# CAN.net
KiCad netlist of a schematic drawn in Altium Designer
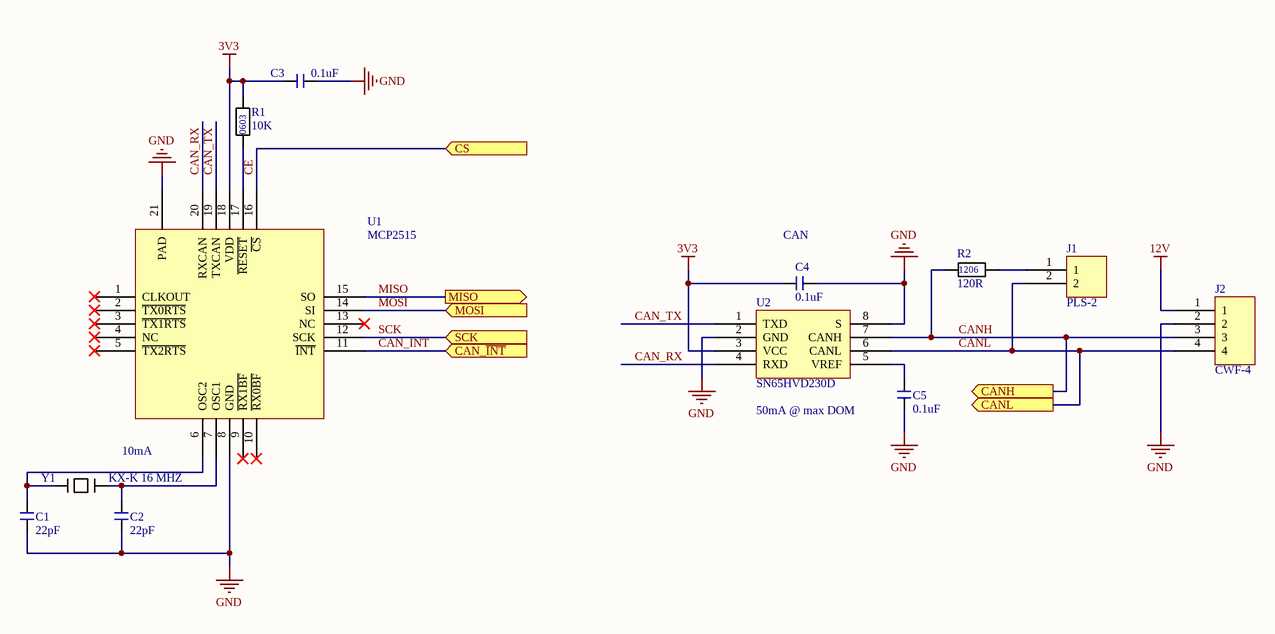
[diagram p0: CAN.SchDoc]

(export (version "E")
  (design (tool "Eeschema 10.0.6"))
  (components
    (comp (ref "C1") (value "22pF") (footprint "CHIP_C_0603") (libsource (lib "Popular") (part "CHIP_C")))
    (comp (ref "C2") (value "22pF") (footprint "CHIP_C_0603") (libsource (lib "Popular") (part "CHIP_C")))
    (comp (ref "C3") (value "0.1uF") (footprint "CHIP_C_0603") (libsource (lib "Popular") (part "CHIP_C")))
    (comp (ref "C4") (value "0.1uF") (footprint "CHIP_C_0603") (libsource (lib "Popular") (part "CHIP_C")))
    (comp (ref "C5") (value "0.1uF") (footprint "CHIP_C_0603") (libsource (lib "Popular") (part "CHIP_C")))
    (comp (ref "J1")
      (value "PLS-2")
      (footprint "PLS-2")
      (description "Connector")
      (libsource (lib "Popular") (part "PLS-2"))
    )
    (comp (ref "J2") (value "CWF-4") (footprint "CWF-4") (libsource (lib "Popular") (part "CWF-4")))
    (comp (ref "R1") (value "10K") (footprint "CHIP_R_0603") (libsource (lib "Popular") (part "RES_0603")))
    (comp (ref "R2") (value "120R") (footprint "CHIP_R_1206") (libsource (lib "Popular") (part "RES_1206")))
    (comp (ref "U1") (value "MCP2515") (footprint "QFN20") (libsource (lib "Popular") (part "MCP2515_QFN")))
    (comp (ref "U2") (value "SN65HVD230D") (footprint "SOIC8") (libsource (lib "Popular") (part "TJA1050")))
    (comp (ref "Y1")
      (value "KX-K 16 MHZ")
      (footprint "CHIP_CRYSTAL_5032")
      (libsource (lib "Popular") (part "Quartz"))
    )
  )
  (nets
    (net (code "1") (name "/CANH") (class "Default")
      (node (ref "J2") (pin "3") (pinfunction "3_3") (pintype "passive"))
      (node (ref "R2") (pin "1") (pinfunction "1_1") (pintype "passive"))
      (node (ref "U2") (pin "7") (pinfunction "CANH_7") (pintype "passive"))
    )
    (net (code "2") (name "/CANL") (class "Default")
      (node (ref "J1") (pin "2") (pinfunction "2_2") (pintype "passive"))
      (node (ref "J2") (pin "4") (pinfunction "4_4") (pintype "passive"))
      (node (ref "U2") (pin "6") (pinfunction "CANL_6") (pintype "passive"))
    )
    (net (code "3") (name "/CAN_RX") (class "Default")
      (node (ref "U1") (pin "20") (pinfunction "RXCAN_20") (pintype "passive"))
      (node (ref "U2") (pin "4") (pinfunction "RXD_4") (pintype "passive"))
    )
    (net (code "4") (name "/CAN_TX") (class "Default")
      (node (ref "U1") (pin "19") (pinfunction "TXCAN_19") (pintype "passive"))
      (node (ref "U2") (pin "1") (pinfunction "TXD_1") (pintype "passive"))
    )
    (net (code "5") (name "/CAN_~{INT}") (class "Default")
      (node (ref "U1") (pin "11") (pinfunction "~{INT}_11") (pintype "passive"))
    )
    (net (code "6") (name "/CE") (class "Default")
      (node (ref "U1") (pin "16") (pinfunction "~{CS}_16") (pintype "passive"))
    )
    (net (code "7") (name "/MISO") (class "Default")
      (node (ref "U1") (pin "15") (pinfunction "SO_15") (pintype "passive"))
    )
    (net (code "8") (name "/MOSI") (class "Default")
      (node (ref "U1") (pin "14") (pinfunction "SI_14") (pintype "passive"))
    )
    (net (code "9") (name "/SCK") (class "Default")
      (node (ref "U1") (pin "12") (pinfunction "SCK_12") (pintype "passive"))
    )
    (net (code "10") (name "3V3") (class "Default")
      (node (ref "C3") (pin "2") (pinfunction "2_2") (pintype "passive"))
      (node (ref "C4") (pin "2") (pinfunction "2_2") (pintype "passive"))
      (node (ref "R1") (pin "2") (pinfunction "2_2") (pintype "passive"))
      (node (ref "U1") (pin "18") (pinfunction "VDD_18") (pintype "passive"))
      (node (ref "U2") (pin "3") (pinfunction "VCC_3") (pintype "passive"))
    )
    (net (code "11") (name "12V") (class "Default")
      (node (ref "J2") (pin "1") (pinfunction "1_1") (pintype "passive"))
    )
    (net (code "12") (name "GND") (class "Default")
      (node (ref "C1") (pin "1") (pinfunction "1_1") (pintype "passive"))
      (node (ref "C2") (pin "1") (pinfunction "1_1") (pintype "passive"))
      (node (ref "C3") (pin "1") (pinfunction "1_1") (pintype "passive"))
      (node (ref "C4") (pin "1") (pinfunction "1_1") (pintype "passive"))
      (node (ref "C5") (pin "1") (pinfunction "1_1") (pintype "passive"))
      (node (ref "J2") (pin "2") (pinfunction "2_2") (pintype "passive"))
      (node (ref "U1") (pin "21") (pinfunction "PAD_21") (pintype "passive"))
      (node (ref "U1") (pin "8") (pinfunction "GND_8") (pintype "passive"))
      (node (ref "U2") (pin "2") (pinfunction "GND_2") (pintype "passive"))
      (node (ref "U2") (pin "8") (pinfunction "S_8") (pintype "passive"))
    )
    (net (code "13") (name "Net-(J1-Pad1)") (class "Default")
      (node (ref "J1") (pin "1") (pinfunction "1_1") (pintype "passive"))
      (node (ref "R2") (pin "2") (pinfunction "2_2") (pintype "passive"))
    )
    (net (code "14") (name "Net-(U1-OSC1)") (class "Default")
      (node (ref "C2") (pin "2") (pinfunction "2_2") (pintype "passive"))
      (node (ref "U1") (pin "7") (pinfunction "OSC1_7") (pintype "passive"))
      (node (ref "Y1") (pin "2") (pinfunction "2_2") (pintype "passive"))
    )
    (net (code "15") (name "Net-(U1-OSC2)") (class "Default")
      (node (ref "C1") (pin "2") (pinfunction "2_2") (pintype "passive"))
      (node (ref "U1") (pin "6") (pinfunction "OSC2_6") (pintype "passive"))
      (node (ref "Y1") (pin "1") (pinfunction "1_1") (pintype "passive"))
    )
    (net (code "16") (name "Net-(U1-~{RESET})") (class "Default")
      (node (ref "R1") (pin "1") (pinfunction "1_1") (pintype "passive"))
      (node (ref "U1") (pin "17") (pinfunction "~{RESET}_17") (pintype "passive"))
    )
    (net (code "17") (name "Net-(U2-VREF)") (class "Default")
      (node (ref "C5") (pin "2") (pinfunction "2_2") (pintype "passive"))
      (node (ref "U2") (pin "5") (pinfunction "VREF_5") (pintype "passive"))
    )
    (net (code "18") (name "unconnected-(U1-CLKOUT-Pad1)") (class "Default")
      (node (ref "U1") (pin "1") (pinfunction "CLKOUT_1") (pintype "passive+no_connect"))
    )
    (net (code "19") (name "unconnected-(U1-NC-Pad4)") (class "Default")
      (node (ref "U1") (pin "4") (pinfunction "NC_4") (pintype "passive+no_connect"))
    )
    (net (code "20") (name "unconnected-(U1-NC-Pad13)") (class "Default")
      (node (ref "U1") (pin "13") (pinfunction "NC_13") (pintype "passive+no_connect"))
    )
    (net (code "21") (name "unconnected-(U1-~{RX0BF}-Pad10)") (class "Default")
      (node (ref "U1") (pin "10") (pinfunction "~{RX0BF}_10") (pintype "passive+no_connect"))
    )
    (net (code "22") (name "unconnected-(U1-~{RX1BF}-Pad9)") (class "Default")
      (node (ref "U1") (pin "9") (pinfunction "~{RX1BF}_9") (pintype "passive+no_connect"))
    )
    (net (code "23") (name "unconnected-(U1-~{TX0RTS}-Pad2)") (class "Default")
      (node (ref "U1") (pin "2") (pinfunction "~{TX0RTS}_2") (pintype "passive+no_connect"))
    )
    (net (code "24") (name "unconnected-(U1-~{TX1RTS}-Pad3)") (class "Default")
      (node (ref "U1") (pin "3") (pinfunction "~{TX1RTS}_3") (pintype "passive+no_connect"))
    )
    (net (code "25") (name "unconnected-(U1-~{TX2RTS}-Pad5)") (class "Default")
      (node (ref "U1") (pin "5") (pinfunction "~{TX2RTS}_5") (pintype "passive+no_connect"))
    )
  )
)
